# LastProject.net
KiCad netlist of a schematic drawn in Altium Designer
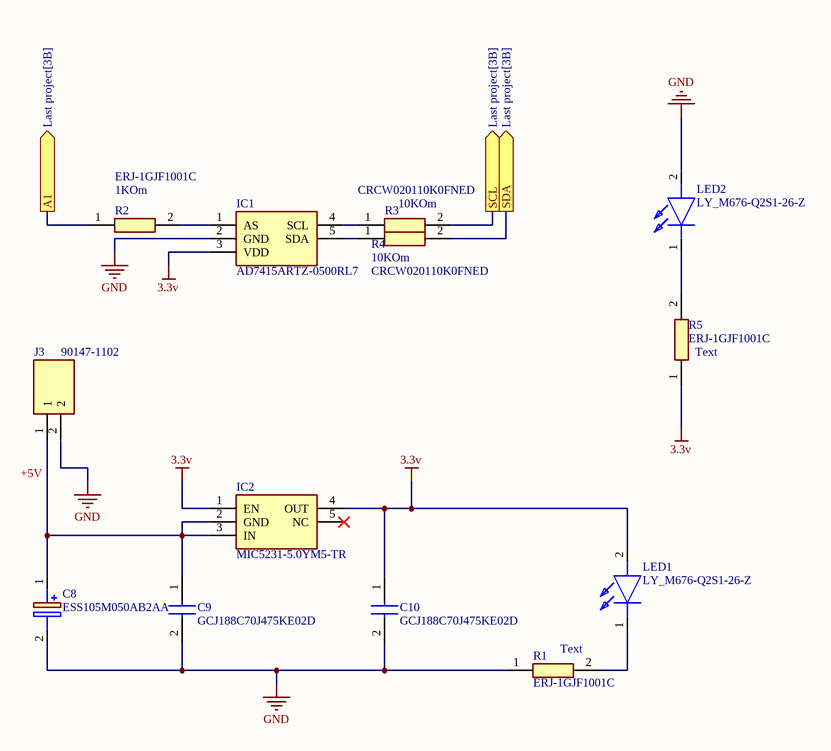
[diagram p0: LastProject.SchDoc]

(export (version "E")
  (design (tool "Eeschema 10.0.6"))
  (components
    (comp (ref "C8")
      (value "ESS105M050AB2AA")
      (footprint "SamacSys:CAPPRD150W45D400H850")
      (description "Capacitor Polarised")
      (fields (field (name "MOUSER PART NUMBER") "80-ESS105M050AB2AA"))
      (libsource (lib "*") (part "ESS105M050AB2AA"))
    )
    (comp (ref "C9")
      (value "GCJ188C70J475KE02D")
      (footprint "SamacSys:CAPC1608X100N")
      (description "Capacitor")
      (fields (field (name "MOUSER PART NUMBER") "81-GCJ188C70J475KE2D"))
      (libsource (lib "*") (part "GCJ188C70J475KE02D"))
    )
    (comp (ref "C10")
      (value "GCJ188C70J475KE02D")
      (footprint "SamacSys:CAPC1608X100N")
      (description "Capacitor")
      (fields (field (name "MOUSER PART NUMBER") "81-GCJ188C70J475KE2D"))
      (libsource (lib "*") (part "GCJ188C70J475KE02D"))
    )
    (comp (ref "IC1")
      (value "AD7415ARTZ-0500RL7")
      (footprint "SamacSys:SOT95P280X145-5N")
      (description "Integrated Circuit")
      (fields (field (name "MOUSER PART NUMBER") "584-AD7415ARTZ0500R7"))
      (libsource (lib "*") (part "AD7415ARTZ-0500RL7"))
    )
    (comp (ref "IC2")
      (value "MIC5231-5.0YM5-TR")
      (footprint "SamacSys:SOT95P280X145-5N")
      (description "Integrated Circuit")
      (fields (field (name "MOUSER PART NUMBER") "998-MIC5231-5.0YM5TR"))
      (libsource (lib "*") (part "MIC5231-5.0YM5-TR"))
    )
    (comp (ref "J3")
      (value "90147-1102")
      (footprint "SamacSys:RHDR2W70P0X254_1X2_493X244X870P")
      (description "Connector")
      (fields (field (name "MOUSER PART NUMBER") "538-90147-1102"))
      (libsource (lib "*") (part "90147-1102"))
    )
    (comp (ref "LED1")
      (value "LY_M676-Q2S1-26-Z")
      (footprint "SamacSys:LYM676Q2S126Z")
      (description "LED")
      (fields
        (field (name "MANUFACTURER_PART_NUMBER") "LY M676-Q2S1-26-Z")
        (field (name "MOUSER PART NUMBER") "720-LYM676Q2S126Z")
      )
      (libsource (lib "*") (part "LY_M676-Q2S1-26-Z"))
    )
    (comp (ref "LED2")
      (value "LY_M676-Q2S1-26-Z")
      (footprint "SamacSys:LYM676Q2S126Z")
      (description "LED")
      (fields
        (field (name "MANUFACTURER_PART_NUMBER") "LY M676-Q2S1-26-Z")
        (field (name "MOUSER PART NUMBER") "720-LYM676Q2S126Z")
      )
      (libsource (lib "*") (part "LY_M676-Q2S1-26-Z"))
    )
    (comp (ref "R1")
      (value "ERJ-1GJF1001C")
      (footprint "SamacSys:ERJ1GJJ2R4C")
      (description "Resistor")
      (fields (field (name "MOUSER PART NUMBER") "667-ERJ-1GJF1001C"))
      (libsource (lib "") (part "ERJ-1GJF1001C_1"))
    )
    (comp (ref "R2")
      (value "ERJ-1GJF1001C")
      (footprint "SamacSys:ERJ1GJJ2R4C")
      (description "Resistor")
      (fields (field (name "MOUSER PART NUMBER") "667-ERJ-1GJF1001C"))
      (libsource (lib "") (part "ERJ-1GJF1001C_1"))
    )
    (comp (ref "R3")
      (value "CRCW020110K0FNED")
      (footprint "SamacSys:RESC0603X28N")
      (description "Resistor")
      (fields (field (name "MOUSER PART NUMBER") "71-CRCW0201-10K"))
      (libsource (lib "*") (part "CRCW020110K0FNED"))
    )
    (comp (ref "R4")
      (value "CRCW020110K0FNED")
      (footprint "SamacSys:RESC0603X28N")
      (description "Resistor")
      (fields (field (name "MOUSER PART NUMBER") "71-CRCW0201-10K"))
      (libsource (lib "*") (part "CRCW020110K0FNED"))
    )
    (comp (ref "R5")
      (value "ERJ-1GJF1001C")
      (footprint "SamacSys:ERJ1GJJ2R4C")
      (description "Resistor")
      (fields (field (name "MOUSER PART NUMBER") "667-ERJ-1GJF1001C"))
      (libsource (lib "*") (part "ERJ-1GJF1001C"))
    )
  )
  (nets
    (net (code "2") (name "/A1") (class "Default")
      (node (ref "R2") (pin "1") (pinfunction "1_1") (pintype "passive"))
    )
    (net (code "3") (name "/SCL") (class "Default")
      (node (ref "R3") (pin "2") (pinfunction "2_2") (pintype "passive"))
    )
    (net (code "4") (name "/SDA") (class "Default")
      (node (ref "R4") (pin "2") (pinfunction "2_2") (pintype "passive"))
    )
    (net (code "5") (name "3.3v") (class "Default")
      (node (ref "C10") (pin "1") (pinfunction "1_1") (pintype "passive"))
      (node (ref "IC1") (pin "3") (pinfunction "VDD_3") (pintype "passive"))
      (node (ref "IC2") (pin "1") (pinfunction "EN_1") (pintype "passive"))
      (node (ref "IC2") (pin "4") (pinfunction "OUT_4") (pintype "passive"))
      (node (ref "LED1") (pin "2") (pinfunction "A_2") (pintype "passive"))
      (node (ref "R5") (pin "1") (pinfunction "1_1") (pintype "passive"))
    )
    (net (code "6") (name "GND") (class "Default")
      (node (ref "C10") (pin "2") (pinfunction "2_2") (pintype "passive"))
      (node (ref "C8") (pin "2") (pinfunction "-_2") (pintype "passive"))
      (node (ref "C9") (pin "2") (pinfunction "2_2") (pintype "passive"))
      (node (ref "IC1") (pin "2") (pinfunction "GND_2") (pintype "passive"))
      (node (ref "J3") (pin "2") (pinfunction "2_2") (pintype "passive"))
      (node (ref "LED2") (pin "2") (pinfunction "A_2") (pintype "passive"))
      (node (ref "R1") (pin "1") (pinfunction "1_1") (pintype "passive"))
    )
    (net (code "7") (name "Net-(C8-+)") (class "Default")
      (node (ref "C8") (pin "1") (pinfunction "+_1") (pintype "passive"))
      (node (ref "C9") (pin "1") (pinfunction "1_1") (pintype "passive"))
      (node (ref "IC2") (pin "2") (pinfunction "GND_2") (pintype "passive"))
      (node (ref "IC2") (pin "3") (pinfunction "IN_3") (pintype "passive"))
      (node (ref "J3") (pin "1") (pinfunction "1_1") (pintype "passive"))
    )
    (net (code "8") (name "Net-(IC1-AS)") (class "Default")
      (node (ref "IC1") (pin "1") (pinfunction "AS_1") (pintype "passive"))
      (node (ref "R2") (pin "2") (pinfunction "2_2") (pintype "passive"))
    )
    (net (code "9") (name "Net-(IC1-SCL)") (class "Default")
      (node (ref "IC1") (pin "4") (pinfunction "SCL_4") (pintype "passive"))
      (node (ref "R3") (pin "1") (pinfunction "1_1") (pintype "passive"))
    )
    (net (code "10") (name "Net-(IC1-SDA)") (class "Default")
      (node (ref "IC1") (pin "5") (pinfunction "SDA_5") (pintype "passive"))
      (node (ref "R4") (pin "1") (pinfunction "1_1") (pintype "passive"))
    )
    (net (code "11") (name "Net-(LED1-K)") (class "Default")
      (node (ref "LED1") (pin "1") (pinfunction "K_1") (pintype "passive"))
      (node (ref "R1") (pin "2") (pinfunction "2_2") (pintype "passive"))
    )
    (net (code "12") (name "Net-(LED2-K)") (class "Default")
      (node (ref "LED2") (pin "1") (pinfunction "K_1") (pintype "passive"))
      (node (ref "R5") (pin "2") (pinfunction "2_2") (pintype "passive"))
    )
    (net (code "13") (name "unconnected-(IC2-NC-Pad5)") (class "Default")
      (node (ref "IC2") (pin "5") (pinfunction "NC_5") (pintype "passive+no_connect"))
    )
  )
)
